# PIC32ETH_Power.net
KiCad netlist of a schematic drawn in Altium Designer
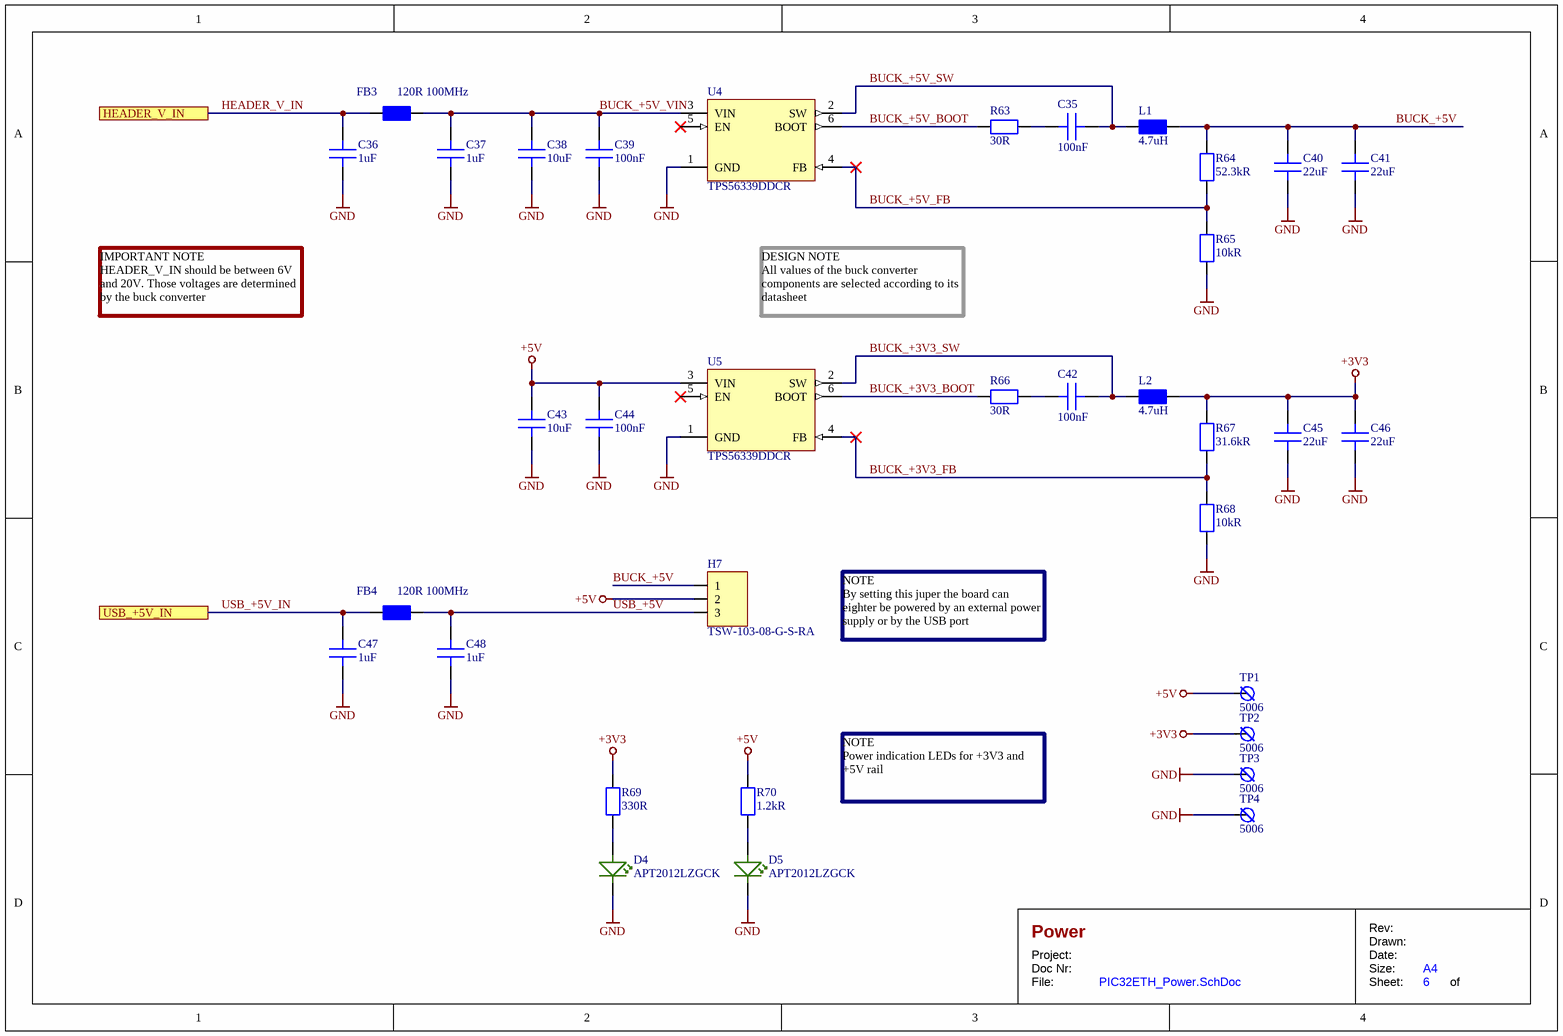
[diagram p0: PIC32ETH_Power.SchDoc]

(export (version "E")
  (design (tool "Eeschema 10.0.6"))
  (components
    (comp (ref "C35")
      (value "100nF")
      (footprint "C_CHIP2012N")
      (description "C CERAMIC 100nF 50V 10% 2012")
      (fields (field (name "MANUFACTURER") "Kemet") (field (name "PART NUMBER") "C0805C104K5RACTU"))
      (libsource (lib "PIC32ETH") (part "C_C0805C104K5RACTU"))
    )
    (comp (ref "C36")
      (value "1uF")
      (footprint "C_CHIP2012N")
      (description "C CERAMIC 1uF 50V 10% 2012")
      (fields (field (name "MANUFACTURER") "Kemet") (field (name "PART NUMBER") "C0805C105K5RACTU"))
      (libsource (lib "PIC32ETH") (part "C_C0805C105K5RACTU"))
    )
    (comp (ref "C37")
      (value "1uF")
      (footprint "C_CHIP2012N")
      (description "C CERAMIC 1uF 50V 10% 2012")
      (fields (field (name "MANUFACTURER") "Kemet") (field (name "PART NUMBER") "C0805C105K5RACTU"))
      (libsource (lib "PIC32ETH") (part "C_C0805C105K5RACTU"))
    )
    (comp (ref "C38")
      (value "10uF")
      (footprint "C_CHIP3216N")
      (description "C CERAMIC 10uF 25V 10% 3216")
      (fields (field (name "PART NUMBER") "C1206C106K3RACTU") (field (name "MANUFACTURER") "Kemet"))
      (libsource (lib "PIC32ETH") (part "C_C1206C106K3RACTU"))
    )
    (comp (ref "C39")
      (value "100nF")
      (footprint "C_CHIP2012N")
      (description "C CERAMIC 100nF 50V 10% 2012")
      (fields (field (name "MANUFACTURER") "Kemet") (field (name "PART NUMBER") "C0805C104K5RACTU"))
      (libsource (lib "PIC32ETH") (part "C_C0805C104K5RACTU"))
    )
    (comp (ref "C40")
      (value "22uF")
      (footprint "C_CHIP3216N")
      (description "C CERAMIC 22uF 10V 10% 3216")
      (fields (field (name "PART NUMBER") "C1206C226K8RAC7800") (field (name "MANUFACTURER") "Kemet"))
      (libsource (lib "PIC32ETH") (part "C_C1206C226K8RAC7800"))
    )
    (comp (ref "C41")
      (value "22uF")
      (footprint "C_CHIP3216N")
      (description "C CERAMIC 22uF 10V 10% 3216")
      (fields (field (name "PART NUMBER") "C1206C226K8RAC7800") (field (name "MANUFACTURER") "Kemet"))
      (libsource (lib "PIC32ETH") (part "C_C1206C226K8RAC7800"))
    )
    (comp (ref "C42")
      (value "100nF")
      (footprint "C_CHIP2012N")
      (description "C CERAMIC 100nF 50V 10% 2012")
      (fields (field (name "MANUFACTURER") "Kemet") (field (name "PART NUMBER") "C0805C104K5RACTU"))
      (libsource (lib "PIC32ETH") (part "C_C0805C104K5RACTU"))
    )
    (comp (ref "C43")
      (value "10uF")
      (footprint "C_CHIP3216N")
      (description "C CERAMIC 10uF 25V 10% 3216")
      (fields (field (name "PART NUMBER") "C1206C106K3RACTU") (field (name "MANUFACTURER") "Kemet"))
      (libsource (lib "PIC32ETH") (part "C_C1206C106K3RACTU"))
    )
    (comp (ref "C44")
      (value "100nF")
      (footprint "C_CHIP2012N")
      (description "C CERAMIC 100nF 50V 10% 2012")
      (fields (field (name "MANUFACTURER") "Kemet") (field (name "PART NUMBER") "C0805C104K5RACTU"))
      (libsource (lib "PIC32ETH") (part "C_C0805C104K5RACTU"))
    )
    (comp (ref "C45")
      (value "22uF")
      (footprint "C_CHIP3216N")
      (description "C CERAMIC 22uF 10V 10% 3216")
      (fields (field (name "PART NUMBER") "C1206C226K8RAC7800") (field (name "MANUFACTURER") "Kemet"))
      (libsource (lib "PIC32ETH") (part "C_C1206C226K8RAC7800"))
    )
    (comp (ref "C46")
      (value "22uF")
      (footprint "C_CHIP3216N")
      (description "C CERAMIC 22uF 10V 10% 3216")
      (fields (field (name "PART NUMBER") "C1206C226K8RAC7800") (field (name "MANUFACTURER") "Kemet"))
      (libsource (lib "PIC32ETH") (part "C_C1206C226K8RAC7800"))
    )
    (comp (ref "C47")
      (value "1uF")
      (footprint "C_CHIP2012N")
      (description "C CERAMIC 1uF 50V 10% 2012")
      (fields (field (name "MANUFACTURER") "Kemet") (field (name "PART NUMBER") "C0805C105K5RACTU"))
      (libsource (lib "PIC32ETH") (part "C_C0805C105K5RACTU"))
    )
    (comp (ref "C48")
      (value "1uF")
      (footprint "C_CHIP2012N")
      (description "C CERAMIC 1uF 50V 10% 2012")
      (fields (field (name "MANUFACTURER") "Kemet") (field (name "PART NUMBER") "C0805C105K5RACTU"))
      (libsource (lib "PIC32ETH") (part "C_C0805C105K5RACTU"))
    )
    (comp (ref "D4")
      (value "APT2012LZGCK")
      (footprint "D_LEDCHIP2012N")
      (description "D LED GREEN CLEAR 2.65V 2mA 2012")
      (fields (field (name "MANUFACTURER") "Kingbright") (field (name "POWER") "102.5mW"))
      (libsource (lib "PIC32ETH") (part "D_APT2012LZGCK"))
    )
    (comp (ref "D5")
      (value "APT2012LZGCK")
      (footprint "D_LEDCHIP2012N")
      (description "D LED GREEN CLEAR 2.65V 2mA 2012")
      (fields (field (name "MANUFACTURER") "Kingbright") (field (name "POWER") "102.5mW"))
      (libsource (lib "PIC32ETH") (part "D_APT2012LZGCK"))
    )
    (comp (ref "FB3")
      (value "120R 100MHz")
      (footprint "FB_CHIP3216N")
      (description "FB 120R 100MHz 6A 3216")
      (fields
        (field (name "MANUFACTURER") "Murata Electronics")
        (field (name "PART NUMBER") "BLM31KN121SN1L")
      )
      (libsource (lib "PIC32ETH") (part "FB_BLM31KN121SN1L"))
    )
    (comp (ref "FB4")
      (value "120R 100MHz")
      (footprint "FB_CHIP3216N")
      (description "FB 120R 100MHz 6A 3216")
      (fields
        (field (name "MANUFACTURER") "Murata Electronics")
        (field (name "PART NUMBER") "BLM31KN121SN1L")
      )
      (libsource (lib "PIC32ETH") (part "FB_BLM31KN121SN1L"))
    )
    (comp (ref "H7")
      (value "TSW-103-08-G-S-RA")
      (footprint "H_TSW-103-08-G-S-RA")
      (description "H GENERAL HEADER 3POS 1ROW 2.54mm ANGLE THT")
      (fields (field (name "MANUFACTURER") "Samtec Inc.") (field (name "VOLTAGE") "550VAC, 770VDC"))
      (libsource (lib "PIC32ETH") (part "H_TSW-103-08-G-S-RA"))
    )
    (comp (ref "L1")
      (value "4.7uH")
      (footprint "L_CHIP2520N")
      (description "L CERAMIC 4.7uH 1.1A 138mR 2520")
      (fields
        (field (name "MANUFACTURER") "Murata Electronics")
        (field (name "PART NUMBER") "LQM2HPN4R7MG0L")
      )
      (libsource (lib "PIC32ETH") (part "L_LQM2HPN4R7MG0L"))
    )
    (comp (ref "L2")
      (value "4.7uH")
      (footprint "L_CHIP2520N")
      (description "L CERAMIC 4.7uH 1.1A 138mR 2520")
      (fields
        (field (name "MANUFACTURER") "Murata Electronics")
        (field (name "PART NUMBER") "LQM2HPN4R7MG0L")
      )
      (libsource (lib "PIC32ETH") (part "L_LQM2HPN4R7MG0L"))
    )
    (comp (ref "R63")
      (value "30R")
      (footprint "R_CHIP2012N")
      (description "R SMT 30R 1% 125mW 2012")
      (fields
        (field (name "MANUFACTURER") "Stackpole Electronics Inc")
        (field (name "PART NUMBER") "RMCF0805FT30R0")
      )
      (libsource (lib "PIC32ETH") (part "R_RMCF0805FT30R0"))
    )
    (comp (ref "R64")
      (value "52.3kR")
      (footprint "R_CHIP2012N")
      (description "R SMT 52.3kR 1% 125mW 2012")
      (fields
        (field (name "MANUFACTURER") "Stackpole Electronics Inc")
        (field (name "PART NUMBER") "RMCF0805FT52K3")
      )
      (libsource (lib "PIC32ETH") (part "R_RMCF0805FT52K3"))
    )
    (comp (ref "R65")
      (value "10kR")
      (footprint "R_CHIP2012N")
      (description "R SMT 10kR 1% 125mW 2012")
      (fields
        (field (name "MANUFACTURER") "Stackpole Electronics Inc")
        (field (name "PART NUMBER") "RMCF0805FT10K0")
      )
      (libsource (lib "PIC32ETH") (part "R_RMCF0805FT10K0"))
    )
    (comp (ref "R66")
      (value "30R")
      (footprint "R_CHIP2012N")
      (description "R SMT 30R 1% 125mW 2012")
      (fields
        (field (name "MANUFACTURER") "Stackpole Electronics Inc")
        (field (name "PART NUMBER") "RMCF0805FT30R0")
      )
      (libsource (lib "PIC32ETH") (part "R_RMCF0805FT30R0"))
    )
    (comp (ref "R67")
      (value "31.6kR")
      (footprint "R_CHIP2012N")
      (description "R SMT 31.6kR 1% 125mW 2012")
      (fields
        (field (name "MANUFACTURER") "Stackpole Electronics Inc")
        (field (name "PART NUMBER") "RMCF0805FT31K6")
      )
      (libsource (lib "PIC32ETH") (part "R_RMCF0805FT31K6"))
    )
    (comp (ref "R68")
      (value "10kR")
      (footprint "R_CHIP2012N")
      (description "R SMT 10kR 1% 125mW 2012")
      (fields
        (field (name "MANUFACTURER") "Stackpole Electronics Inc")
        (field (name "PART NUMBER") "RMCF0805FT10K0")
      )
      (libsource (lib "PIC32ETH") (part "R_RMCF0805FT10K0"))
    )
    (comp (ref "R69")
      (value "330R")
      (footprint "R_CHIP2012N")
      (description "R SMT 330R 1% 125mW 2012")
      (fields
        (field (name "MANUFACTURER") "Stackpole Electronics Inc")
        (field (name "PART NUMBER") "RMCF0805FT330R")
      )
      (libsource (lib "PIC32ETH") (part "R_RMCF0805FT330R"))
    )
    (comp (ref "R70")
      (value "1.2kR")
      (footprint "R_CHIP2012N")
      (description "R SMT 1.2kR 1% 125mW 2012")
      (fields
        (field (name "MANUFACTURER") "Stackpole Electronics Inc")
        (field (name "PART NUMBER") "RMCF0805FT1K20")
      )
      (libsource (lib "PIC32ETH") (part "R_RMCF0805FT1K20"))
    )
    (comp (ref "TP1")
      (value "5006")
      (footprint "TP_5006")
      (description "TP COMPACT BLACK THT")
      (fields (field (name "MANUFACTURER") "Keystone Electronics") (field (name "VOLTAGE") "n/a"))
      (libsource (lib "PIC32ETH") (part "TP_5006"))
    )
    (comp (ref "TP2")
      (value "5006")
      (footprint "TP_5006")
      (description "TP COMPACT BLACK THT")
      (fields (field (name "MANUFACTURER") "Keystone Electronics") (field (name "VOLTAGE") "n/a"))
      (libsource (lib "PIC32ETH") (part "TP_5006"))
    )
    (comp (ref "TP3")
      (value "5006")
      (footprint "TP_5006")
      (description "TP COMPACT BLACK THT")
      (fields (field (name "MANUFACTURER") "Keystone Electronics") (field (name "VOLTAGE") "n/a"))
      (libsource (lib "PIC32ETH") (part "TP_5006"))
    )
    (comp (ref "TP4")
      (value "5006")
      (footprint "TP_5006")
      (description "TP COMPACT BLACK THT")
      (fields (field (name "MANUFACTURER") "Keystone Electronics") (field (name "VOLTAGE") "n/a"))
      (libsource (lib "PIC32ETH") (part "TP_5006"))
    )
    (comp (ref "U4")
      (value "TPS56339DDCR")
      (footprint "U_SOT95P280X145-6N")
      (description "U REGULATOR BUCK 0.8V TO 16V 3A SOT-23-6")
      (fields (field (name "MANUFACTURER") "Texas Instruments"))
      (libsource (lib "PIC32ETH") (part "U_TPS56339DDCR"))
    )
    (comp (ref "U5")
      (value "TPS56339DDCR")
      (footprint "U_SOT95P280X145-6N")
      (description "U REGULATOR BUCK 0.8V TO 16V 3A SOT-23-6")
      (fields (field (name "MANUFACTURER") "Texas Instruments"))
      (libsource (lib "PIC32ETH") (part "U_TPS56339DDCR"))
    )
  )
  (nets
    (net (code "1") (name "+3V3") (class "Default")
      (node (ref "C45") (pin "2") (pinfunction "2_2") (pintype "passive"))
      (node (ref "C46") (pin "2") (pinfunction "2_2") (pintype "passive"))
      (node (ref "L2") (pin "2") (pinfunction "2_2") (pintype "passive"))
      (node (ref "R67") (pin "2") (pinfunction "2_2") (pintype "passive"))
      (node (ref "R69") (pin "2") (pinfunction "2_2") (pintype "passive"))
      (node (ref "TP2") (pin "1") (pinfunction "A_1") (pintype "passive"))
    )
    (net (code "2") (name "+5V") (class "Default")
      (node (ref "C43") (pin "2") (pinfunction "2_2") (pintype "passive"))
      (node (ref "C44") (pin "2") (pinfunction "2_2") (pintype "passive"))
      (node (ref "H7") (pin "2") (pinfunction "2_2") (pintype "passive"))
      (node (ref "R70") (pin "2") (pinfunction "2_2") (pintype "passive"))
      (node (ref "TP1") (pin "1") (pinfunction "A_1") (pintype "passive"))
      (node (ref "U5") (pin "3") (pinfunction "VIN_3") (pintype "power_in"))
    )
    (net (code "3") (name "/BUCK_+3V3_BOOT") (class "Default")
      (node (ref "R66") (pin "1") (pinfunction "1_1") (pintype "passive"))
      (node (ref "U5") (pin "6") (pinfunction "BOOT_6") (pintype "output"))
    )
    (net (code "4") (name "/BUCK_+3V3_FB") (class "Default")
      (node (ref "R67") (pin "1") (pinfunction "1_1") (pintype "passive"))
      (node (ref "R68") (pin "2") (pinfunction "2_2") (pintype "passive"))
      (node (ref "U5") (pin "4") (pinfunction "FB_4") (pintype "input"))
    )
    (net (code "5") (name "/BUCK_+3V3_SW") (class "Default")
      (node (ref "C42") (pin "1") (pinfunction "1_1") (pintype "passive"))
      (node (ref "L2") (pin "1") (pinfunction "1_1") (pintype "passive"))
      (node (ref "U5") (pin "2") (pinfunction "SW_2") (pintype "output"))
    )
    (net (code "6") (name "/BUCK_+5V") (class "Default")
      (node (ref "C40") (pin "2") (pinfunction "2_2") (pintype "passive"))
      (node (ref "C41") (pin "2") (pinfunction "2_2") (pintype "passive"))
      (node (ref "H7") (pin "1") (pinfunction "1_1") (pintype "passive"))
      (node (ref "L1") (pin "2") (pinfunction "2_2") (pintype "passive"))
      (node (ref "R64") (pin "2") (pinfunction "2_2") (pintype "passive"))
    )
    (net (code "7") (name "/BUCK_+5V_BOOT") (class "Default")
      (node (ref "R63") (pin "1") (pinfunction "1_1") (pintype "passive"))
      (node (ref "U4") (pin "6") (pinfunction "BOOT_6") (pintype "output"))
    )
    (net (code "8") (name "/BUCK_+5V_FB") (class "Default")
      (node (ref "R64") (pin "1") (pinfunction "1_1") (pintype "passive"))
      (node (ref "R65") (pin "2") (pinfunction "2_2") (pintype "passive"))
      (node (ref "U4") (pin "4") (pinfunction "FB_4") (pintype "input"))
    )
    (net (code "9") (name "/BUCK_+5V_SW") (class "Default")
      (node (ref "C35") (pin "1") (pinfunction "1_1") (pintype "passive"))
      (node (ref "L1") (pin "1") (pinfunction "1_1") (pintype "passive"))
      (node (ref "U4") (pin "2") (pinfunction "SW_2") (pintype "output"))
    )
    (net (code "10") (name "/BUCK_+5V_VIN") (class "Default")
      (node (ref "C37") (pin "2") (pinfunction "2_2") (pintype "passive"))
      (node (ref "C38") (pin "2") (pinfunction "2_2") (pintype "passive"))
      (node (ref "C39") (pin "2") (pinfunction "2_2") (pintype "passive"))
      (node (ref "FB3") (pin "2") (pinfunction "2_2") (pintype "passive"))
      (node (ref "U4") (pin "3") (pinfunction "VIN_3") (pintype "power_in"))
    )
    (net (code "11") (name "/HEADER_V_IN") (class "Default")
      (node (ref "C36") (pin "2") (pinfunction "2_2") (pintype "passive"))
      (node (ref "FB3") (pin "1") (pinfunction "1_1") (pintype "passive"))
    )
    (net (code "12") (name "/USB_+5V") (class "Default")
      (node (ref "C48") (pin "2") (pinfunction "2_2") (pintype "passive"))
      (node (ref "FB4") (pin "2") (pinfunction "2_2") (pintype "passive"))
      (node (ref "H7") (pin "3") (pinfunction "3_3") (pintype "passive"))
    )
    (net (code "13") (name "/USB_+5V_IN") (class "Default")
      (node (ref "C47") (pin "2") (pinfunction "2_2") (pintype "passive"))
      (node (ref "FB4") (pin "1") (pinfunction "1_1") (pintype "passive"))
    )
    (net (code "14") (name "GND") (class "Default")
      (node (ref "C36") (pin "1") (pinfunction "1_1") (pintype "passive"))
      (node (ref "C37") (pin "1") (pinfunction "1_1") (pintype "passive"))
      (node (ref "C38") (pin "1") (pinfunction "1_1") (pintype "passive"))
      (node (ref "C39") (pin "1") (pinfunction "1_1") (pintype "passive"))
      (node (ref "C40") (pin "1") (pinfunction "1_1") (pintype "passive"))
      (node (ref "C41") (pin "1") (pinfunction "1_1") (pintype "passive"))
      (node (ref "C43") (pin "1") (pinfunction "1_1") (pintype "passive"))
      (node (ref "C44") (pin "1") (pinfunction "1_1") (pintype "passive"))
      (node (ref "C45") (pin "1") (pinfunction "1_1") (pintype "passive"))
      (node (ref "C46") (pin "1") (pinfunction "1_1") (pintype "passive"))
      (node (ref "C47") (pin "1") (pinfunction "1_1") (pintype "passive"))
      (node (ref "C48") (pin "1") (pinfunction "1_1") (pintype "passive"))
      (node (ref "D4") (pin "1") (pinfunction "1_1") (pintype "passive"))
      (node (ref "D5") (pin "1") (pinfunction "1_1") (pintype "passive"))
      (node (ref "R65") (pin "1") (pinfunction "1_1") (pintype "passive"))
      (node (ref "R68") (pin "1") (pinfunction "1_1") (pintype "passive"))
      (node (ref "TP3") (pin "1") (pinfunction "A_1") (pintype "passive"))
      (node (ref "TP4") (pin "1") (pinfunction "A_1") (pintype "passive"))
      (node (ref "U4") (pin "1") (pinfunction "GND_1") (pintype "power_in"))
      (node (ref "U5") (pin "1") (pinfunction "GND_1") (pintype "power_in"))
    )
    (net (code "15") (name "Net-(C35-Pad2)") (class "Default")
      (node (ref "C35") (pin "2") (pinfunction "2_2") (pintype "passive"))
      (node (ref "R63") (pin "2") (pinfunction "2_2") (pintype "passive"))
    )
    (net (code "16") (name "Net-(C42-Pad2)") (class "Default")
      (node (ref "C42") (pin "2") (pinfunction "2_2") (pintype "passive"))
      (node (ref "R66") (pin "2") (pinfunction "2_2") (pintype "passive"))
    )
    (net (code "17") (name "Net-(D4-Pad2)") (class "Default")
      (node (ref "D4") (pin "2") (pinfunction "2_2") (pintype "passive"))
      (node (ref "R69") (pin "1") (pinfunction "1_1") (pintype "passive"))
    )
    (net (code "18") (name "Net-(D5-Pad2)") (class "Default")
      (node (ref "D5") (pin "2") (pinfunction "2_2") (pintype "passive"))
      (node (ref "R70") (pin "1") (pinfunction "1_1") (pintype "passive"))
    )
    (net (code "19") (name "unconnected-(U4-EN-Pad5)") (class "Default")
      (node (ref "U4") (pin "5") (pinfunction "EN_5") (pintype "input+no_connect"))
    )
    (net (code "20") (name "unconnected-(U5-EN-Pad5)") (class "Default")
      (node (ref "U5") (pin "5") (pinfunction "EN_5") (pintype "input+no_connect"))
    )
  )
)
